# ReflowController.net
KiCad netlist of a schematic drawn in EAGLE
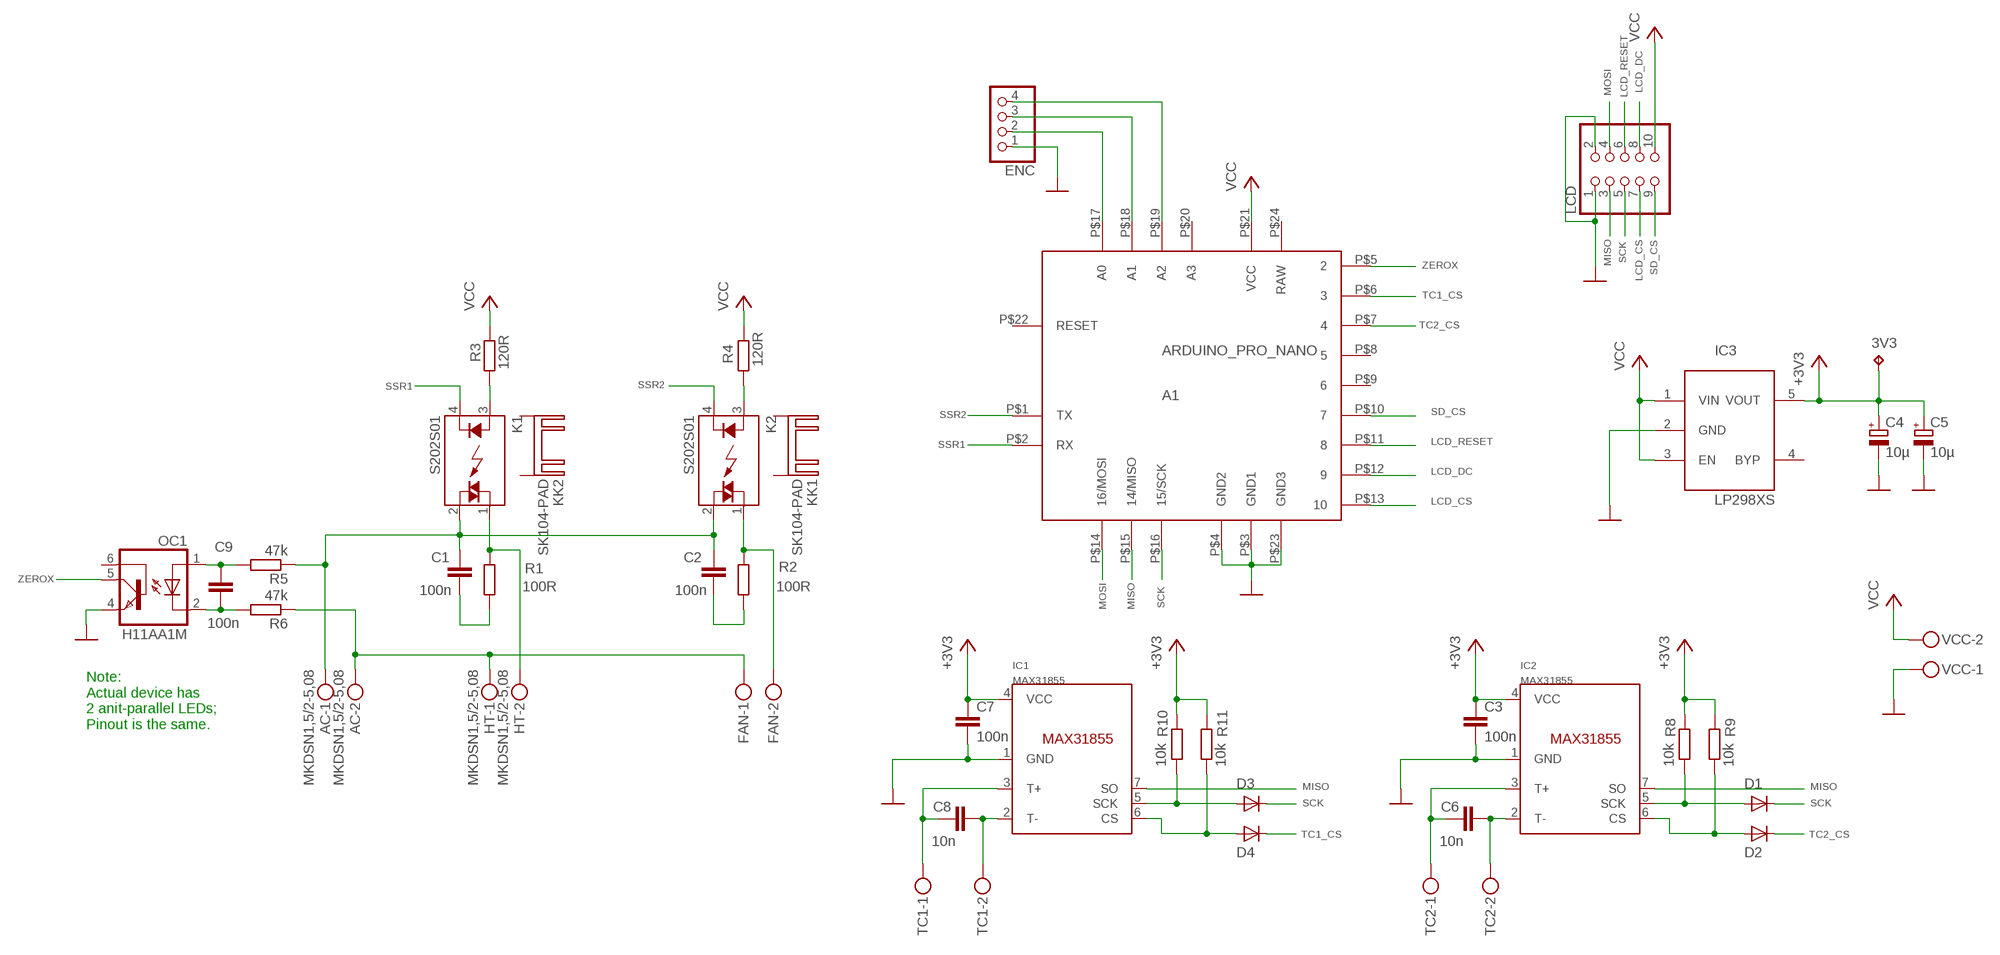
[diagram p0: schematic, sheet 1]

(export (version "E")
  (design (tool "Eeschema 10.0.6"))
  (components
    (comp (ref "3V3")
      (value "TPTP08R")
      (footprint "eagle-import:TP08R")
      (libsource (lib "eagle-import") (part "TPTP08R"))
    )
    (comp (ref "A1")
      (value "ARDUINO_PRO_NANO")
      (footprint "eagle-import:ARDUINO_PRO_NANO")
      (libsource (lib "eagle-import") (part "ARDUINO_PRO_NANO"))
    )
    (comp (ref "AC")
      (value "MKDSN1,5/2-5,08")
      (footprint "eagle-import:MKDSN1,5_2-5,08")
      (fields (field (name "MPN") "MKDSN 1,5/2-5.08"))
      (libsource (lib "eagle-import") (part "MKDSN1,5/2-5,08"))
    )
    (comp (ref "C1")
      (value "100n")
      (footprint "eagle-import:XC10B5")
      (libsource (lib "eagle-import") (part "CXXC10B5"))
    )
    (comp (ref "C2")
      (value "100n")
      (footprint "eagle-import:XC10B5")
      (libsource (lib "eagle-import") (part "CXXC10B5"))
    )
    (comp (ref "C3")
      (value "100n")
      (footprint "eagle-import:C0805")
      (libsource (lib "eagle-import") (part "C-EUC0805"))
    )
    (comp (ref "C4")
      (value "10µ")
      (footprint "eagle-import:C_6032-28R")
      (libsource (lib "eagle-import") (part "CPOL-EUC/6032-28R"))
    )
    (comp (ref "C5")
      (value "10µ")
      (footprint "eagle-import:C_6032-28R")
      (libsource (lib "eagle-import") (part "CPOL-EUC/6032-28R"))
    )
    (comp (ref "C6")
      (value "10n")
      (footprint "eagle-import:C0603")
      (libsource (lib "eagle-import") (part "C-EUC0603"))
    )
    (comp (ref "C7")
      (value "100n")
      (footprint "eagle-import:C0805")
      (libsource (lib "eagle-import") (part "C-EUC0805"))
    )
    (comp (ref "C8")
      (value "10n")
      (footprint "eagle-import:C0603")
      (libsource (lib "eagle-import") (part "C-EUC0603"))
    )
    (comp (ref "C9")
      (value "100n")
      (footprint "eagle-import:C025-025X050")
      (libsource (lib "eagle-import") (part "C-EU025-025X050"))
    )
    (comp (ref "D1")
      (value "DIODESOD-123")
      (footprint "eagle-import:SOD-123")
      (libsource (lib "eagle-import") (part "DIODESOD-123"))
    )
    (comp (ref "D2")
      (value "DIODESOD-123")
      (footprint "eagle-import:SOD-123")
      (libsource (lib "eagle-import") (part "DIODESOD-123"))
    )
    (comp (ref "D3")
      (value "DIODESOD-123")
      (footprint "eagle-import:SOD-123")
      (libsource (lib "eagle-import") (part "DIODESOD-123"))
    )
    (comp (ref "D4")
      (value "DIODESOD-123")
      (footprint "eagle-import:SOD-123")
      (libsource (lib "eagle-import") (part "DIODESOD-123"))
    )
    (comp (ref "ENC")
      (value "PINHD-1X4")
      (footprint "eagle-import:1X04")
      (libsource (lib "eagle-import") (part "PINHD-1X4"))
    )
    (comp (ref "FAN")
      (value "MKDSN1,5/2-5,08")
      (footprint "eagle-import:MKDSN1,5_2-5,08")
      (fields (field (name "MPN") "MKDSN 1,5/2-5.08"))
      (libsource (lib "eagle-import") (part "MKDSN1,5/2-5,08"))
    )
    (comp (ref "HT")
      (value "MKDSN1,5/2-5,08")
      (footprint "eagle-import:MKDSN1,5_2-5,08")
      (fields (field (name "MPN") "MKDSN 1,5/2-5.08"))
      (libsource (lib "eagle-import") (part "MKDSN1,5/2-5,08"))
    )
    (comp (ref "IC1")
      (value "MAX31855")
      (footprint "eagle-import:SOIC8")
      (libsource (lib "eagle-import") (part "MAX31855"))
    )
    (comp (ref "IC2")
      (value "MAX31855")
      (footprint "eagle-import:SOIC8")
      (libsource (lib "eagle-import") (part "MAX31855"))
    )
    (comp (ref "IC3")
      (value "LP298XS")
      (footprint "eagle-import:SOT23-5L")
      (libsource (lib "eagle-import") (part "LP298XS"))
    )
    (comp (ref "K1")
      (value "S202S01")
      (footprint "eagle-import:S102S01")
      (fields (field (name "MPN") "S202S01F"))
      (libsource (lib "eagle-import") (part "S?202S01"))
    )
    (comp (ref "K2")
      (value "S202S01")
      (footprint "eagle-import:S102S01")
      (fields (field (name "MPN") "S202S01F"))
      (libsource (lib "eagle-import") (part "S?202S01"))
    )
    (comp (ref "KK1")
      (value "SK104-PAD")
      (footprint "eagle-import:SK104-PAD")
      (libsource (lib "eagle-import") (part "SK104-PAD"))
    )
    (comp (ref "KK2")
      (value "SK104-PAD")
      (footprint "eagle-import:SK104-PAD")
      (libsource (lib "eagle-import") (part "SK104-PAD"))
    )
    (comp (ref "LCD")
      (value "PINHD-2X5")
      (footprint "eagle-import:2X05")
      (libsource (lib "eagle-import") (part "PINHD-2X5"))
    )
    (comp (ref "OC1")
      (value "H11AA1M")
      (footprint "eagle-import:DIL06")
      (fields (field (name "MPN") "H11A1-M"))
      (libsource (lib "eagle-import") (part "H11A?M1"))
    )
    (comp (ref "R1")
      (value "100R")
      (footprint "eagle-import:0207_5V")
      (libsource (lib "eagle-import") (part "R-EU_0207/5V"))
    )
    (comp (ref "R2")
      (value "100R")
      (footprint "eagle-import:0207_5V")
      (libsource (lib "eagle-import") (part "R-EU_0207/5V"))
    )
    (comp (ref "R3")
      (value "120R")
      (footprint "eagle-import:R0603")
      (libsource (lib "eagle-import") (part "R-EU_R0603"))
    )
    (comp (ref "R4")
      (value "120R")
      (footprint "eagle-import:R0603")
      (libsource (lib "eagle-import") (part "R-EU_R0603"))
    )
    (comp (ref "R5")
      (value "47k")
      (footprint "eagle-import:0207_5V")
      (libsource (lib "eagle-import") (part "R-EU_0207/5V"))
    )
    (comp (ref "R6")
      (value "47k")
      (footprint "eagle-import:0207_5V")
      (libsource (lib "eagle-import") (part "R-EU_0207/5V"))
    )
    (comp (ref "R8")
      (value "10k")
      (footprint "eagle-import:R0603")
      (libsource (lib "eagle-import") (part "R-EU_R0603"))
    )
    (comp (ref "R9")
      (value "10k")
      (footprint "eagle-import:R0603")
      (libsource (lib "eagle-import") (part "R-EU_R0603"))
    )
    (comp (ref "R10")
      (value "10k")
      (footprint "eagle-import:R0603")
      (libsource (lib "eagle-import") (part "R-EU_R0603"))
    )
    (comp (ref "R11")
      (value "10k")
      (footprint "eagle-import:R0603")
      (libsource (lib "eagle-import") (part "R-EU_R0603"))
    )
    (comp (ref "TC1")
      (value "MKDSN1,5/2-5,08")
      (footprint "eagle-import:MKDSN1,5_2-5,08")
      (fields (field (name "MPN") "MKDSN 1,5/2-5.08"))
      (libsource (lib "eagle-import") (part "MKDSN1,5/2-5,08"))
    )
    (comp (ref "TC2")
      (value "MKDSN1,5/2-5,08")
      (footprint "eagle-import:MKDSN1,5_2-5,08")
      (fields (field (name "MPN") "MKDSN 1,5/2-5.08"))
      (libsource (lib "eagle-import") (part "MKDSN1,5/2-5,08"))
    )
    (comp (ref "VCC")
      (value "MKDSN1,5/2-5,08")
      (footprint "eagle-import:MKDSN1,5_2-5,08")
      (fields (field (name "MPN") "MKDSN 1,5/2-5.08"))
      (libsource (lib "eagle-import") (part "MKDSN1,5/2-5,08"))
    )
  )
  (nets
    (net (code "1") (name "+3V3") (class "Default")
      (node (ref "3V3") (pin "TP") (pinfunction "TP_TP") (pintype "input"))
      (node (ref "C3") (pin "1") (pinfunction "1_1") (pintype "passive"))
      (node (ref "C4") (pin "+") (pinfunction "+_+") (pintype "passive"))
      (node (ref "C5") (pin "+") (pinfunction "+_+") (pintype "passive"))
      (node (ref "C7") (pin "1") (pinfunction "1_1") (pintype "passive"))
      (node (ref "IC1") (pin "4") (pinfunction "VCC_4") (pintype "power_in"))
      (node (ref "IC2") (pin "4") (pinfunction "VCC_4") (pintype "power_in"))
      (node (ref "IC3") (pin "5") (pinfunction "VOUT_5") (pintype "bidirectional"))
      (node (ref "R10") (pin "2") (pinfunction "2_2") (pintype "passive"))
      (node (ref "R11") (pin "2") (pinfunction "2_2") (pintype "passive"))
      (node (ref "R8") (pin "2") (pinfunction "2_2") (pintype "passive"))
      (node (ref "R9") (pin "2") (pinfunction "2_2") (pintype "passive"))
    )
    (net (code "2") (name "/LCD_CS") (class "Default")
      (node (ref "A1") (pin "P$13") (pinfunction "10_P$13") (pintype "bidirectional"))
      (node (ref "LCD") (pin "7") (pinfunction "7_7") (pintype "passive"))
    )
    (net (code "3") (name "/LCD_DC") (class "Default")
      (node (ref "A1") (pin "P$12") (pinfunction "9_P$12") (pintype "bidirectional"))
      (node (ref "LCD") (pin "8") (pinfunction "8_8") (pintype "passive"))
    )
    (net (code "4") (name "/LCD_RESET") (class "Default")
      (node (ref "A1") (pin "P$11") (pinfunction "8_P$11") (pintype "bidirectional"))
      (node (ref "LCD") (pin "6") (pinfunction "6_6") (pintype "passive"))
    )
    (net (code "5") (name "/MISO") (class "Default")
      (node (ref "A1") (pin "P$15") (pinfunction "14/MISO_P$15") (pintype "bidirectional"))
      (node (ref "IC1") (pin "7") (pinfunction "SO_7") (pintype "output"))
      (node (ref "IC2") (pin "7") (pinfunction "SO_7") (pintype "output"))
      (node (ref "LCD") (pin "3") (pinfunction "3_3") (pintype "passive"))
    )
    (net (code "6") (name "/MOSI") (class "Default")
      (node (ref "A1") (pin "P$14") (pinfunction "16/MOSI_P$14") (pintype "bidirectional"))
      (node (ref "LCD") (pin "4") (pinfunction "4_4") (pintype "passive"))
    )
    (net (code "7") (name "/RAW") (class "Default")
      (node (ref "A1") (pin "P$24") (pinfunction "RAW_P$24") (pintype "power_in"))
    )
    (net (code "8") (name "/SCK") (class "Default")
      (node (ref "A1") (pin "P$16") (pinfunction "15/SCK_P$16") (pintype "bidirectional"))
      (node (ref "D1") (pin "C") (pinfunction "C_C") (pintype "passive"))
      (node (ref "D3") (pin "C") (pinfunction "C_C") (pintype "passive"))
      (node (ref "LCD") (pin "5") (pinfunction "5_5") (pintype "passive"))
    )
    (net (code "9") (name "/SD_CS") (class "Default")
      (node (ref "A1") (pin "P$10") (pinfunction "7_P$10") (pintype "bidirectional"))
      (node (ref "LCD") (pin "9") (pinfunction "9_9") (pintype "passive"))
    )
    (net (code "10") (name "/SSR1") (class "Default")
      (node (ref "A1") (pin "P$2") (pinfunction "RX_P$2") (pintype "bidirectional"))
      (node (ref "K1") (pin "4") (pinfunction "K_4") (pintype "passive"))
    )
    (net (code "11") (name "/SSR2") (class "Default")
      (node (ref "A1") (pin "P$1") (pinfunction "TX_P$1") (pintype "bidirectional"))
      (node (ref "K2") (pin "4") (pinfunction "K_4") (pintype "passive"))
    )
    (net (code "12") (name "/TC1_CS") (class "Default")
      (node (ref "A1") (pin "P$6") (pinfunction "3_P$6") (pintype "bidirectional"))
      (node (ref "D4") (pin "C") (pinfunction "C_C") (pintype "passive"))
    )
    (net (code "13") (name "/TC2_CS") (class "Default")
      (node (ref "A1") (pin "P$7") (pinfunction "4_P$7") (pintype "bidirectional"))
      (node (ref "D2") (pin "C") (pinfunction "C_C") (pintype "passive"))
    )
    (net (code "14") (name "/ZEROX") (class "Default")
      (node (ref "A1") (pin "P$5") (pinfunction "2_P$5") (pintype "bidirectional"))
      (node (ref "OC1") (pin "5") (pinfunction "COL_5") (pintype "passive"))
    )
    (net (code "15") (name "GND") (class "Default")
      (node (ref "A1") (pin "P$23") (pinfunction "GND3_P$23") (pintype "power_in"))
      (node (ref "A1") (pin "P$3") (pinfunction "GND1_P$3") (pintype "power_in"))
      (node (ref "A1") (pin "P$4") (pinfunction "GND2_P$4") (pintype "power_in"))
      (node (ref "C3") (pin "2") (pinfunction "2_2") (pintype "passive"))
      (node (ref "C4") (pin "-") (pinfunction "-_-") (pintype "passive"))
      (node (ref "C5") (pin "-") (pinfunction "-_-") (pintype "passive"))
      (node (ref "C7") (pin "2") (pinfunction "2_2") (pintype "passive"))
      (node (ref "ENC") (pin "1") (pinfunction "1_1") (pintype "passive"))
      (node (ref "IC1") (pin "1") (pinfunction "GND_1") (pintype "power_in"))
      (node (ref "IC2") (pin "1") (pinfunction "GND_1") (pintype "power_in"))
      (node (ref "IC3") (pin "2") (pinfunction "GND_2") (pintype "bidirectional"))
      (node (ref "LCD") (pin "1") (pinfunction "1_1") (pintype "passive"))
      (node (ref "LCD") (pin "2") (pinfunction "2_2") (pintype "passive"))
      (node (ref "OC1") (pin "4") (pinfunction "EMI_4") (pintype "passive"))
      (node (ref "VCC") (pin "1") (pinfunction "KL_1") (pintype "passive"))
    )
    (net (code "16") (name "Net-(A1-A0)") (class "Default")
      (node (ref "A1") (pin "P$17") (pinfunction "A0_P$17") (pintype "bidirectional"))
      (node (ref "ENC") (pin "2") (pinfunction "2_2") (pintype "passive"))
    )
    (net (code "17") (name "Net-(A1-A1)") (class "Default")
      (node (ref "A1") (pin "P$18") (pinfunction "A1_P$18") (pintype "bidirectional"))
      (node (ref "ENC") (pin "3") (pinfunction "3_3") (pintype "passive"))
    )
    (net (code "18") (name "Net-(A1-A2)") (class "Default")
      (node (ref "A1") (pin "P$19") (pinfunction "A2_P$19") (pintype "bidirectional"))
      (node (ref "ENC") (pin "4") (pinfunction "4_4") (pintype "passive"))
    )
    (net (code "19") (name "Net-(ACA-KL)") (class "Default")
      (node (ref "AC") (pin "1") (pinfunction "KL_1") (pintype "passive"))
      (node (ref "C1") (pin "1") (pinfunction "1_1") (pintype "passive"))
      (node (ref "C2") (pin "1") (pinfunction "1_1") (pintype "passive"))
      (node (ref "K1") (pin "2") (pinfunction "DS2_2") (pintype "passive"))
      (node (ref "K2") (pin "2") (pinfunction "DS2_2") (pintype "passive"))
      (node (ref "R5") (pin "1") (pinfunction "1_1") (pintype "passive"))
    )
    (net (code "20") (name "Net-(ACB-KL)") (class "Default")
      (node (ref "AC") (pin "2") (pinfunction "KL_2") (pintype "passive"))
      (node (ref "FAN") (pin "1") (pinfunction "KL_1") (pintype "passive"))
      (node (ref "HT") (pin "1") (pinfunction "KL_1") (pintype "passive"))
      (node (ref "R6") (pin "1") (pinfunction "1_1") (pintype "passive"))
    )
    (net (code "21") (name "Net-(C1-Pad2)") (class "Default")
      (node (ref "C1") (pin "2") (pinfunction "2_2") (pintype "passive"))
      (node (ref "R1") (pin "1") (pinfunction "1_1") (pintype "passive"))
    )
    (net (code "22") (name "Net-(C2-Pad2)") (class "Default")
      (node (ref "C2") (pin "2") (pinfunction "2_2") (pintype "passive"))
      (node (ref "R2") (pin "1") (pinfunction "1_1") (pintype "passive"))
    )
    (net (code "23") (name "Net-(FANB-KL)") (class "Default")
      (node (ref "FAN") (pin "2") (pinfunction "KL_2") (pintype "passive"))
      (node (ref "K2") (pin "1") (pinfunction "DS1_1") (pintype "passive"))
      (node (ref "R2") (pin "2") (pinfunction "2_2") (pintype "passive"))
    )
    (net (code "24") (name "Net-(HTB-KL)") (class "Default")
      (node (ref "HT") (pin "2") (pinfunction "KL_2") (pintype "passive"))
      (node (ref "K1") (pin "1") (pinfunction "DS1_1") (pintype "passive"))
      (node (ref "R1") (pin "2") (pinfunction "2_2") (pintype "passive"))
    )
    (net (code "25") (name "Net-(IC1-CS)") (class "Default")
      (node (ref "D4") (pin "A") (pinfunction "A_A") (pintype "passive"))
      (node (ref "IC1") (pin "6") (pinfunction "CS_6") (pintype "input"))
      (node (ref "R11") (pin "1") (pinfunction "1_1") (pintype "passive"))
    )
    (net (code "26") (name "Net-(IC1-SCK)") (class "Default")
      (node (ref "D3") (pin "A") (pinfunction "A_A") (pintype "passive"))
      (node (ref "IC1") (pin "5") (pinfunction "SCK_5") (pintype "input"))
      (node (ref "R10") (pin "1") (pinfunction "1_1") (pintype "passive"))
    )
    (net (code "27") (name "Net-(IC1-T+)") (class "Default")
      (node (ref "C8") (pin "1") (pinfunction "1_1") (pintype "passive"))
      (node (ref "IC1") (pin "3") (pinfunction "T+_3") (pintype "input"))
      (node (ref "TC1") (pin "1") (pinfunction "KL_1") (pintype "passive"))
    )
    (net (code "28") (name "Net-(IC1-T-)") (class "Default")
      (node (ref "C8") (pin "2") (pinfunction "2_2") (pintype "passive"))
      (node (ref "IC1") (pin "2") (pinfunction "T-_2") (pintype "input"))
      (node (ref "TC1") (pin "2") (pinfunction "KL_2") (pintype "passive"))
    )
    (net (code "29") (name "Net-(IC2-CS)") (class "Default")
      (node (ref "D2") (pin "A") (pinfunction "A_A") (pintype "passive"))
      (node (ref "IC2") (pin "6") (pinfunction "CS_6") (pintype "input"))
      (node (ref "R9") (pin "1") (pinfunction "1_1") (pintype "passive"))
    )
    (net (code "30") (name "Net-(IC2-SCK)") (class "Default")
      (node (ref "D1") (pin "A") (pinfunction "A_A") (pintype "passive"))
      (node (ref "IC2") (pin "5") (pinfunction "SCK_5") (pintype "input"))
      (node (ref "R8") (pin "1") (pinfunction "1_1") (pintype "passive"))
    )
    (net (code "31") (name "Net-(IC2-T+)") (class "Default")
      (node (ref "C6") (pin "1") (pinfunction "1_1") (pintype "passive"))
      (node (ref "IC2") (pin "3") (pinfunction "T+_3") (pintype "input"))
      (node (ref "TC2") (pin "1") (pinfunction "KL_1") (pintype "passive"))
    )
    (net (code "32") (name "Net-(IC2-T-)") (class "Default")
      (node (ref "C6") (pin "2") (pinfunction "2_2") (pintype "passive"))
      (node (ref "IC2") (pin "2") (pinfunction "T-_2") (pintype "input"))
      (node (ref "TC2") (pin "2") (pinfunction "KL_2") (pintype "passive"))
    )
    (net (code "33") (name "Net-(K1-A)") (class "Default")
      (node (ref "K1") (pin "3") (pinfunction "A_3") (pintype "passive"))
      (node (ref "R3") (pin "2") (pinfunction "2_2") (pintype "passive"))
    )
    (net (code "34") (name "Net-(K2-A)") (class "Default")
      (node (ref "K2") (pin "3") (pinfunction "A_3") (pintype "passive"))
      (node (ref "R4") (pin "2") (pinfunction "2_2") (pintype "passive"))
    )
    (net (code "35") (name "Net-(OC1-A)") (class "Default")
      (node (ref "C9") (pin "1") (pinfunction "1_1") (pintype "passive"))
      (node (ref "OC1") (pin "1") (pinfunction "A_1") (pintype "passive"))
      (node (ref "R5") (pin "2") (pinfunction "2_2") (pintype "passive"))
    )
    (net (code "36") (name "Net-(OC1-C)") (class "Default")
      (node (ref "C9") (pin "2") (pinfunction "2_2") (pintype "passive"))
      (node (ref "OC1") (pin "2") (pinfunction "C_2") (pintype "passive"))
      (node (ref "R6") (pin "2") (pinfunction "2_2") (pintype "passive"))
    )
    (net (code "37") (name "VCC") (class "Default")
      (node (ref "A1") (pin "P$21") (pinfunction "VCC_P$21") (pintype "power_in"))
      (node (ref "IC3") (pin "1") (pinfunction "VIN_1") (pintype "bidirectional"))
      (node (ref "IC3") (pin "3") (pinfunction "EN_3") (pintype "bidirectional"))
      (node (ref "LCD") (pin "10") (pinfunction "10_10") (pintype "passive"))
      (node (ref "R3") (pin "1") (pinfunction "1_1") (pintype "passive"))
      (node (ref "R4") (pin "1") (pinfunction "1_1") (pintype "passive"))
      (node (ref "VCC") (pin "2") (pinfunction "KL_2") (pintype "passive"))
    )
    (net (code "38") (name "unconnected-(A1-5-PadP$8)") (class "Default")
      (node (ref "A1") (pin "P$8") (pinfunction "5_P$8") (pintype "bidirectional"))
    )
    (net (code "39") (name "unconnected-(A1-6-PadP$9)") (class "Default")
      (node (ref "A1") (pin "P$9") (pinfunction "6_P$9") (pintype "bidirectional"))
    )
    (net (code "40") (name "unconnected-(A1-A3-PadP$20)") (class "Default")
      (node (ref "A1") (pin "P$20") (pinfunction "A3_P$20") (pintype "bidirectional"))
    )
    (net (code "41") (name "unconnected-(A1-RESET-PadP$22)") (class "Default")
      (node (ref "A1") (pin "P$22") (pinfunction "RESET_P$22") (pintype "bidirectional"))
    )
    (net (code "42") (name "unconnected-(IC3-BYP-Pad4)") (class "Default")
      (node (ref "IC3") (pin "4") (pinfunction "BYP_4") (pintype "bidirectional"))
    )
    (net (code "43") (name "unconnected-(KK1-K-PadK1)") (class "Default")
      (node (ref "KK1") (pin "K1") (pinfunction "K_K1") (pintype "passive"))
    )
    (net (code "44") (name "unconnected-(KK1-K-PadK2)") (class "Default")
      (node (ref "KK1") (pin "K2") (pinfunction "K_K2") (pintype "passive"))
    )
    (net (code "45") (name "unconnected-(KK2-K-PadK1)") (class "Default")
      (node (ref "KK2") (pin "K1") (pinfunction "K_K1") (pintype "passive"))
    )
    (net (code "46") (name "unconnected-(KK2-K-PadK2)") (class "Default")
      (node (ref "KK2") (pin "K2") (pinfunction "K_K2") (pintype "passive"))
    )
    (net (code "47") (name "unconnected-(OC1-BAS-Pad6)") (class "Default")
      (node (ref "OC1") (pin "6") (pinfunction "BAS_6") (pintype "passive"))
    )
  )
)
